# V4-Add1W-V01-010.net
KiCad netlist of a schematic drawn in EAGLE
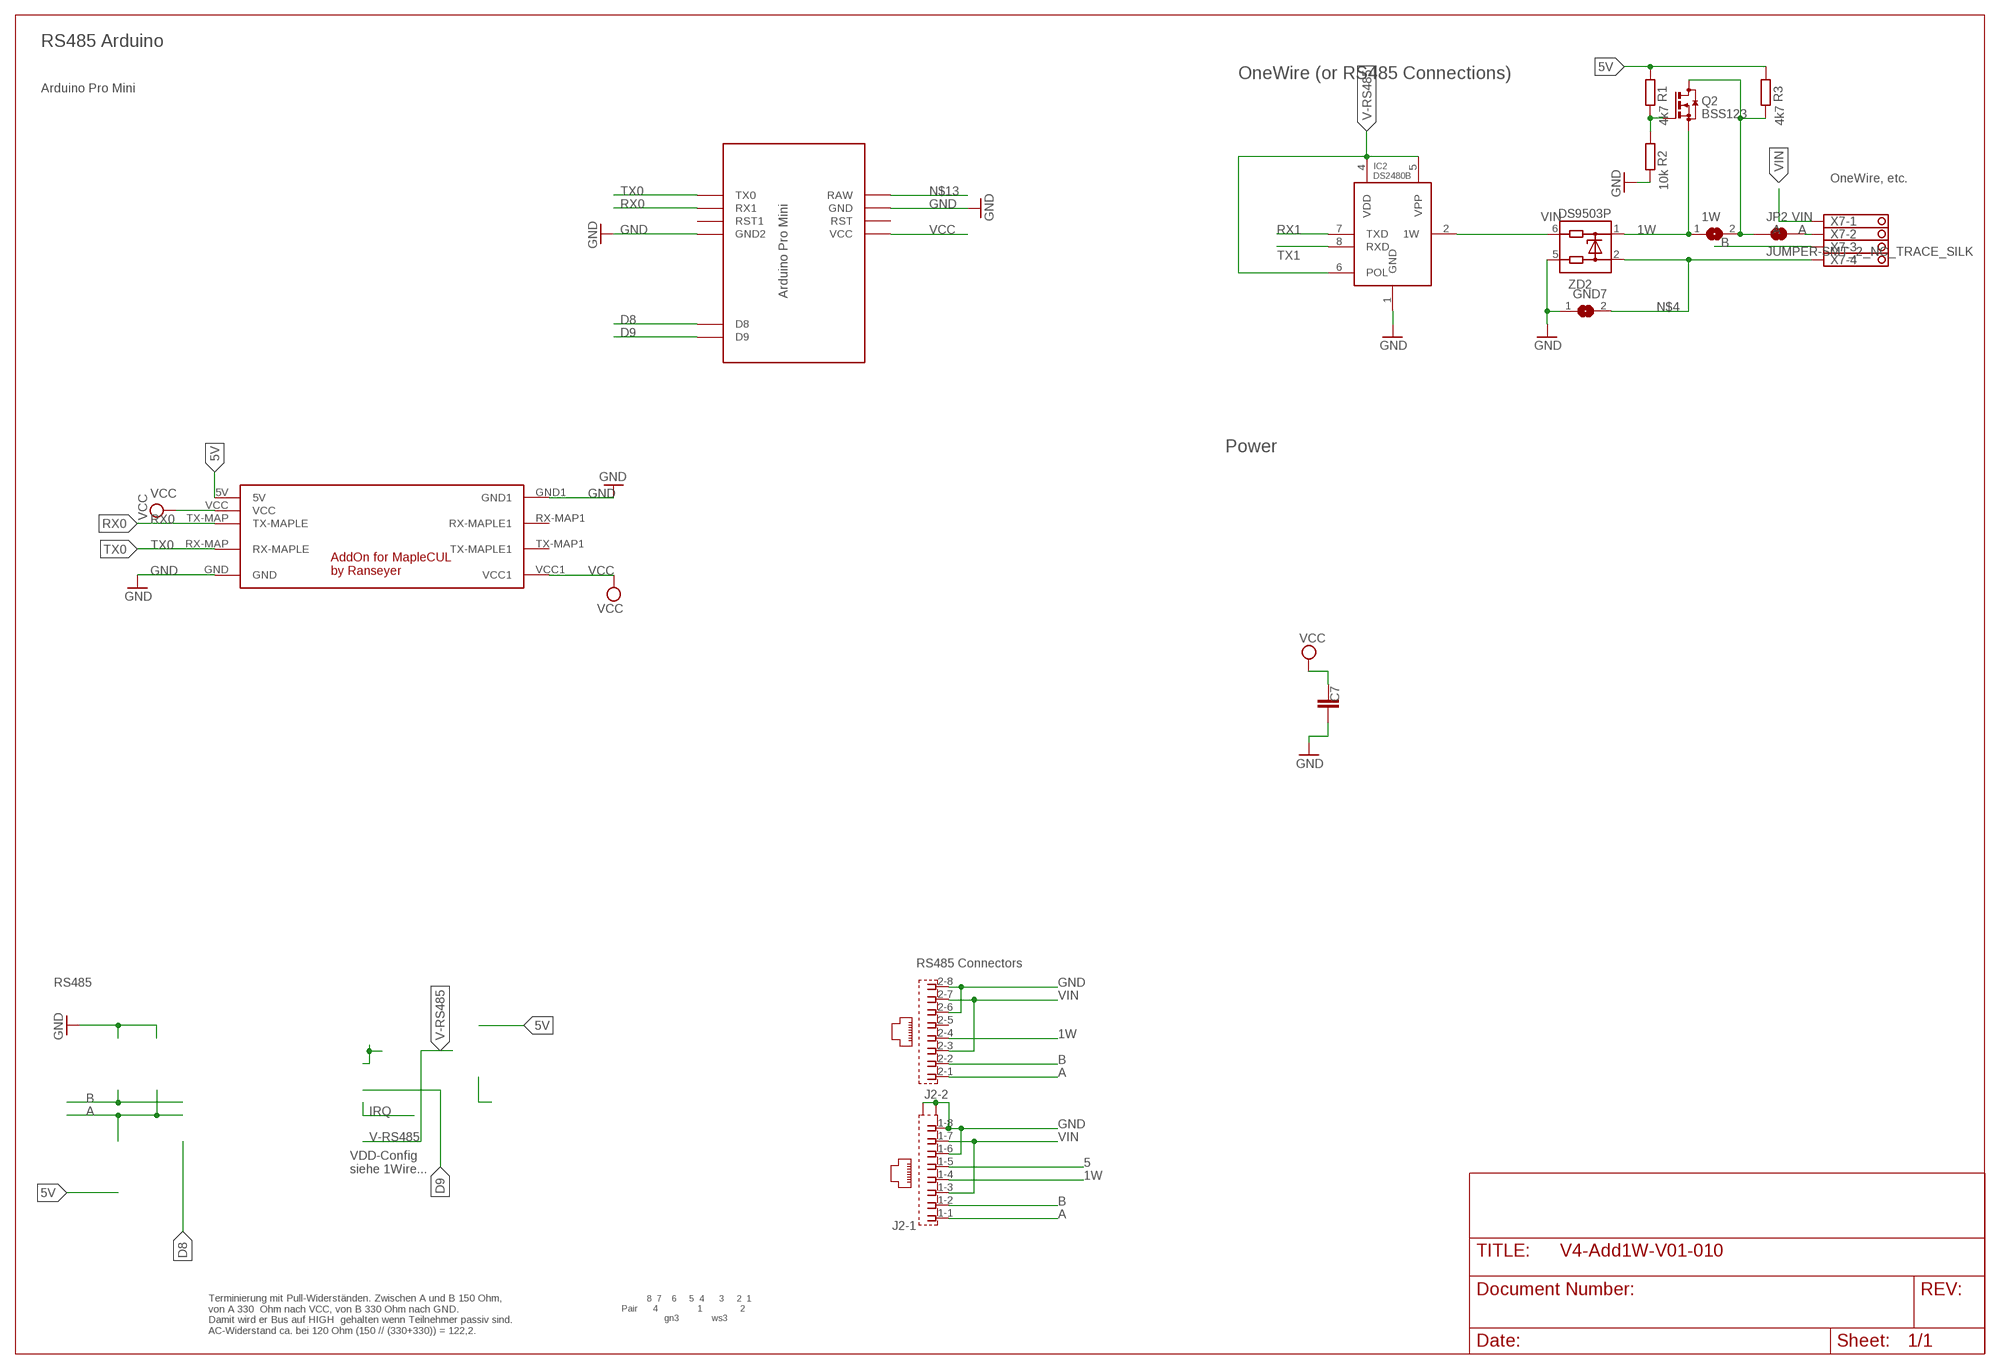
[diagram p0: schematic, sheet 1]

(export (version "E")
  (design (tool "Eeschema 10.0.6"))
  (components
    (comp (ref "1W") (value "SJ") (footprint "eagle-import:SJ") (libsource (lib "eagle-import") (part "SJ")))
    (comp (ref "C7")
      (value "C-EUC1812")
      (footprint "eagle-import:C1812")
      (libsource (lib "eagle-import") (part "C-EUC1812"))
    )
    (comp (ref "GND7")
      (value "SJ")
      (footprint "eagle-import:SJ")
      (libsource (lib "eagle-import") (part "SJ"))
    )
    (comp (ref "IC2")
      (value "DS2480B")
      (footprint "eagle-import:SO08")
      (libsource (lib "eagle-import") (part "DS2480B"))
    )
    (comp (ref "J2")
      (value "RJ45_2X_S")
      (footprint "eagle-import:RJ45_2X_S")
      (libsource (lib "eagle-import") (part "RJ45_2X_S"))
    )
    (comp (ref "JP2")
      (value "JUMPER-SMT_2_NC_TRACE_SILK")
      (footprint "eagle-import:SMT-JUMPER_2_NC_TRACE_SILK")
      (libsource (lib "eagle-import") (part "JUMPER-SMT_2_NC_TRACE_SILK"))
    )
    (comp (ref "Q2")
      (value "BSS123")
      (footprint "eagle-import:SOT23")
      (libsource (lib "eagle-import") (part "BSS123"))
    )
    (comp (ref "R1")
      (value "4k7")
      (footprint "eagle-import:R0805")
      (libsource (lib "eagle-import") (part "R-EU_R0805"))
    )
    (comp (ref "R2")
      (value "10k")
      (footprint "eagle-import:R0805")
      (libsource (lib "eagle-import") (part "R-EU_R0805"))
    )
    (comp (ref "R3")
      (value "4k7")
      (footprint "eagle-import:R0805")
      (libsource (lib "eagle-import") (part "R-EU_R0805"))
    )
    (comp (ref "U$2")
      (value "MAPLE-CUL-ADDON-V01")
      (footprint "eagle-import:MAPLE-CUL-V01")
      (libsource (lib "eagle-import") (part "MAPLE-CUL-ADDON-V01"))
    )
    (comp (ref "U$3")
      (value "MARTIN-PRO-MINI-RS485")
      (footprint "eagle-import:MARTIN-PRO-MINI-RS485")
      (libsource (lib "eagle-import") (part "MARTIN-PRO-MINI-RS485"))
    )
    (comp (ref "X7")
      (value "1751264")
      (footprint "eagle-import:1751264")
      (libsource (lib "eagle-import") (part "1751264"))
    )
    (comp (ref "ZD2")
      (value "DS9503P")
      (footprint "eagle-import:TSOC6")
      (libsource (lib "eagle-import") (part "DS9503P"))
    )
  )
  (nets
    (net (code "1") (name "/1W") (class "Default")
      (node (ref "1W") (pin "1") (pinfunction "1_1") (pintype "passive"))
      (node (ref "J2") (pin "1-4") (pinfunction "4_1-4") (pintype "passive"))
      (node (ref "J2") (pin "2-4") (pinfunction "4_2-4") (pintype "passive"))
      (node (ref "Q2") (pin "2") (pinfunction "S_2") (pintype "passive"))
      (node (ref "ZD2") (pin "1") (pinfunction "P$1_1") (pintype "passive"))
    )
    (net (code "2") (name "/5") (class "Default")
      (node (ref "J2") (pin "1-5") (pinfunction "5_1-5") (pintype "passive"))
    )
    (net (code "3") (name "/A") (class "Default")
      (node (ref "1W") (pin "2") (pinfunction "2_2") (pintype "passive"))
      (node (ref "J2") (pin "1-1") (pinfunction "1_1-1") (pintype "passive"))
      (node (ref "J2") (pin "2-1") (pinfunction "1_2-1") (pintype "passive"))
      (node (ref "JP2") (pin "1") (pinfunction "1_1") (pintype "passive"))
      (node (ref "JP2") (pin "2") (pinfunction "2_2") (pintype "passive"))
      (node (ref "Q2") (pin "3") (pinfunction "D_3") (pintype "passive"))
      (node (ref "R3") (pin "2") (pinfunction "2_2") (pintype "passive"))
      (node (ref "X7") (pin "2") (pinfunction "K_2") (pintype "passive"))
    )
    (net (code "4") (name "/B") (class "Default")
      (node (ref "J2") (pin "1-2") (pinfunction "2_1-2") (pintype "passive"))
      (node (ref "J2") (pin "2-2") (pinfunction "2_2-2") (pintype "passive"))
      (node (ref "X7") (pin "3") (pinfunction "K_3") (pintype "passive"))
    )
    (net (code "6") (name "/N$4") (class "Default")
      (node (ref "GND7") (pin "2") (pinfunction "2_2") (pintype "passive"))
      (node (ref "X7") (pin "4") (pinfunction "K_4") (pintype "passive"))
      (node (ref "ZD2") (pin "2") (pinfunction "P$2_2") (pintype "passive"))
    )
    (net (code "7") (name "/N$13") (class "Default")
      (node (ref "U$3") (pin "RAW") (pinfunction "RAW_RAW") (pintype "bidirectional"))
    )
    (net (code "8") (name "/RX1") (class "Default")
      (node (ref "IC2") (pin "7") (pinfunction "TXD_7") (pintype "input"))
    )
    (net (code "9") (name "/TX1") (class "Default")
      (node (ref "IC2") (pin "8") (pinfunction "RXD_8") (pintype "output"))
    )
    (net (code "10") (name "5V") (class "Default")
      (node (ref "R1") (pin "1") (pinfunction "1_1") (pintype "passive"))
      (node (ref "R3") (pin "1") (pinfunction "1_1") (pintype "passive"))
      (node (ref "U$2") (pin "5V") (pinfunction "5V_5V") (pintype "bidirectional"))
    )
    (net (code "11") (name "D8") (class "Default")
      (node (ref "U$3") (pin "D8") (pinfunction "D8_D8") (pintype "bidirectional"))
    )
    (net (code "12") (name "D9") (class "Default")
      (node (ref "U$3") (pin "D9") (pinfunction "D9_D9") (pintype "bidirectional"))
    )
    (net (code "13") (name "GND") (class "Default")
      (node (ref "C7") (pin "1") (pinfunction "1_1") (pintype "passive"))
      (node (ref "GND7") (pin "1") (pinfunction "1_1") (pintype "passive"))
      (node (ref "IC2") (pin "1") (pinfunction "GND_1") (pintype "power_in"))
      (node (ref "J2") (pin "1-6") (pinfunction "6_1-6") (pintype "passive"))
      (node (ref "J2") (pin "1-8") (pinfunction "8_1-8") (pintype "passive"))
      (node (ref "J2") (pin "2-6") (pinfunction "6_2-6") (pintype "passive"))
      (node (ref "J2") (pin "2-8") (pinfunction "8_2-8") (pintype "passive"))
      (node (ref "J2") (pin "G1") (pinfunction "S2_G1") (pintype "passive"))
      (node (ref "J2") (pin "G3") (pinfunction "S1_G3") (pintype "passive"))
      (node (ref "R2") (pin "2") (pinfunction "2_2") (pintype "passive"))
      (node (ref "U$2") (pin "GND") (pinfunction "GND_GND") (pintype "bidirectional"))
      (node (ref "U$2") (pin "GND1") (pinfunction "GND1_GND1") (pintype "bidirectional"))
      (node (ref "U$3") (pin "GND") (pinfunction "GND_GND") (pintype "bidirectional"))
      (node (ref "U$3") (pin "GND1") (pinfunction "GND2_GND1") (pintype "bidirectional"))
      (node (ref "ZD2") (pin "5") (pinfunction "P$3_5") (pintype "passive"))
    )
    (net (code "14") (name "Net-(IC2-1W)") (class "Default")
      (node (ref "IC2") (pin "2") (pinfunction "1W_2") (pintype "open_collector"))
      (node (ref "ZD2") (pin "6") (pinfunction "P$4_6") (pintype "passive"))
    )
    (net (code "15") (name "Net-(Q2-G)") (class "Default")
      (node (ref "Q2") (pin "1") (pinfunction "G_1") (pintype "passive"))
      (node (ref "R1") (pin "2") (pinfunction "2_2") (pintype "passive"))
      (node (ref "R2") (pin "1") (pinfunction "1_1") (pintype "passive"))
    )
    (net (code "16") (name "RX0") (class "Default")
      (node (ref "U$2") (pin "TX-MAP") (pinfunction "TX-MAPLE_TX-MAP") (pintype "bidirectional"))
      (node (ref "U$3") (pin "RX1") (pinfunction "RX1_RX1") (pintype "bidirectional"))
    )
    (net (code "17") (name "TX0") (class "Default")
      (node (ref "U$2") (pin "RX-MAP") (pinfunction "RX-MAPLE_RX-MAP") (pintype "bidirectional"))
      (node (ref "U$3") (pin "TX0") (pinfunction "TX0_TX0") (pintype "bidirectional"))
    )
    (net (code "18") (name "V-RS485") (class "Default")
      (node (ref "IC2") (pin "4") (pinfunction "VDD_4") (pintype "power_in"))
      (node (ref "IC2") (pin "5") (pinfunction "VPP_5") (pintype "power_in"))
      (node (ref "IC2") (pin "6") (pinfunction "POL_6") (pintype "input"))
    )
    (net (code "19") (name "VCC") (class "Default")
      (node (ref "C7") (pin "2") (pinfunction "2_2") (pintype "passive"))
      (node (ref "U$2") (pin "VCC") (pinfunction "VCC_VCC") (pintype "bidirectional"))
      (node (ref "U$2") (pin "VCC1") (pinfunction "VCC1_VCC1") (pintype "bidirectional"))
      (node (ref "U$3") (pin "VCC") (pinfunction "VCC_VCC") (pintype "bidirectional"))
    )
    (net (code "20") (name "VIN") (class "Default")
      (node (ref "J2") (pin "1-3") (pinfunction "3_1-3") (pintype "passive"))
      (node (ref "J2") (pin "1-7") (pinfunction "7_1-7") (pintype "passive"))
      (node (ref "J2") (pin "2-3") (pinfunction "3_2-3") (pintype "passive"))
      (node (ref "J2") (pin "2-7") (pinfunction "7_2-7") (pintype "passive"))
      (node (ref "X7") (pin "1") (pinfunction "K_1") (pintype "passive"))
    )
    (net (code "21") (name "unconnected-(J2B-5-Pad2-5)") (class "Default")
      (node (ref "J2") (pin "2-5") (pinfunction "5_2-5") (pintype "passive"))
    )
    (net (code "22") (name "unconnected-(U$2-RX-MAPLE1-PadRX-MAP1)") (class "Default")
      (node (ref "U$2") (pin "RX-MAP1") (pinfunction "RX-MAPLE1_RX-MAP1") (pintype "bidirectional"))
    )
    (net (code "23") (name "unconnected-(U$2-TX-MAPLE1-PadTX-MAP1)") (class "Default")
      (node (ref "U$2") (pin "TX-MAP1") (pinfunction "TX-MAPLE1_TX-MAP1") (pintype "bidirectional"))
    )
    (net (code "24") (name "unconnected-(U$3-PadRST)") (class "Default")
      (node (ref "U$3") (pin "RST") (pinfunction "RST_RST") (pintype "bidirectional"))
    )
    (net (code "25") (name "unconnected-(U$3-PadRST1)") (class "Default")
      (node (ref "U$3") (pin "RST1") (pinfunction "RST1_RST1") (pintype "bidirectional"))
    )
  )
)
